# CT_switching.net
KiCad netlist of a schematic drawn in Altium Designer
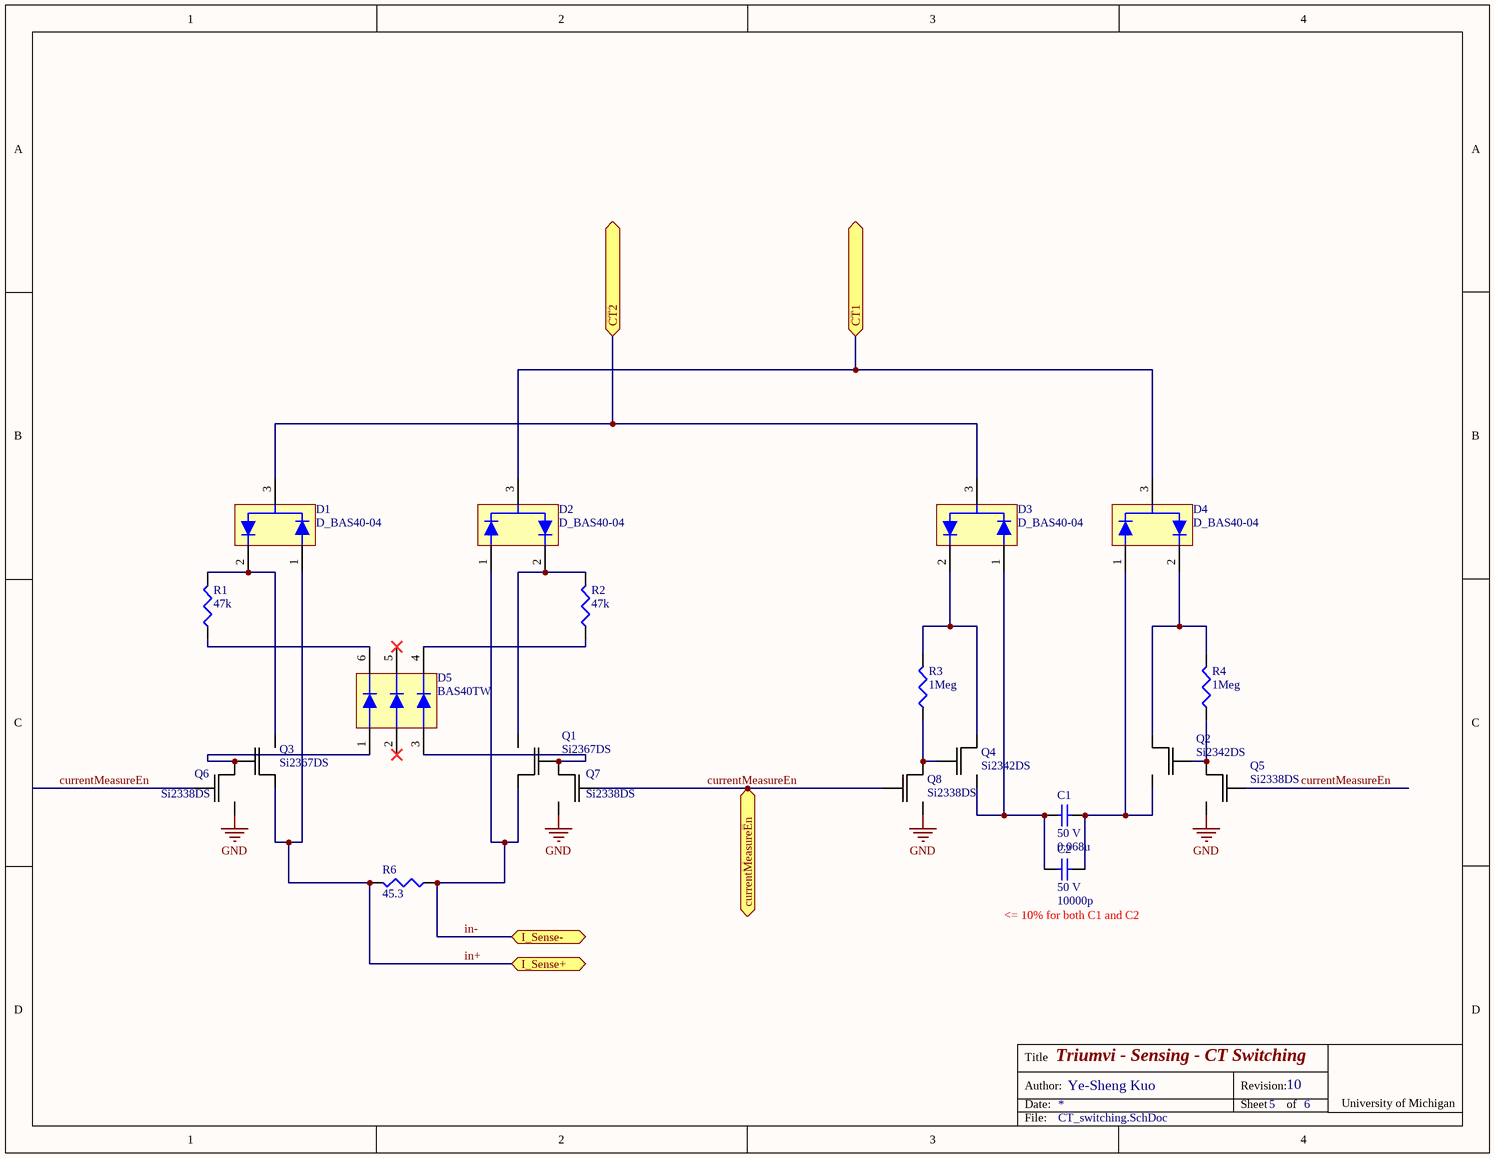
[diagram p0: CT_switching.SchDoc]

(export (version "E")
  (design (tool "Eeschema 10.0.6"))
  (components
    (comp (ref "C1")
      (value "0.068u")
      (footprint "0603")
      (description "0.068µF ±10% 50V Ceramic Capacitor X7R 0603")
      (fields
        (field (name "TOLERANCE") "10%")
        (field (name "VOLTAGE RATED") "50 V")
        (field (name "MANUFACTURER PART NUMBER") "C0603C683K5RACTU")
      )
      (libsource (lib "capacitors") (part "C0603C683K5RACTU"))
    )
    (comp (ref "C2")
      (value "10000p")
      (footprint "0603")
      (description "10000pF ±5% 50V Ceramic Capacitor X7R 0603")
      (fields
        (field (name "TOLERANCE") "5%")
        (field (name "VOLTAGE RATED") "50 V")
        (field (name "MANUFACTURER PART NUMBER") "C0603C103J5RACTU")
      )
      (libsource (lib "capacitors") (part "C0603C103J5RACTU"))
    )
    (comp (ref "D1")
      (value "D_BAS40-04")
      (footprint "SOT23-3")
      (description "SURFACE MOUNT SCHOTTKY BARRIER DIODE")
      (libsource (lib "diodes") (part "D_BAS40-04"))
    )
    (comp (ref "D2")
      (value "D_BAS40-04")
      (footprint "SOT23-3")
      (description "SURFACE MOUNT SCHOTTKY BARRIER DIODE")
      (libsource (lib "") (part "D_BAS40-04_1"))
    )
    (comp (ref "D3")
      (value "D_BAS40-04")
      (footprint "SOT23-3")
      (description "SURFACE MOUNT SCHOTTKY BARRIER DIODE")
      (libsource (lib "diodes") (part "D_BAS40-04"))
    )
    (comp (ref "D4")
      (value "D_BAS40-04")
      (footprint "SOT23-3")
      (description "SURFACE MOUNT SCHOTTKY BARRIER DIODE")
      (libsource (lib "") (part "D_BAS40-04_1"))
    )
    (comp (ref "D5")
      (value "BAS40TW")
      (footprint "SOT-363")
      (description "SURFACE MOUNT SCHOTTKY BARRIER DIODE ARRAYS")
      (libsource (lib "diodes") (part "D_BAS40TW"))
    )
    (comp (ref "Q1")
      (value "Si2367DS")
      (footprint "SOT23-3")
      (description "P-Channel 20 V (D-S) MOSFET")
      (libsource (lib "transistors") (part "Si2367DS"))
    )
    (comp (ref "Q2")
      (value "Si2342DS")
      (footprint "SOT23-3")
      (description "N-Channel 8 V (D-S) MOSFET")
      (libsource (lib "transistors") (part "Si2342DS"))
    )
    (comp (ref "Q3")
      (value "Si2367DS")
      (footprint "SOT23-3")
      (description "P-Channel 20 V (D-S) MOSFET")
      (libsource (lib "transistors") (part "Si2367DS"))
    )
    (comp (ref "Q4")
      (value "Si2342DS")
      (footprint "SOT23-3")
      (description "N-Channel 8 V (D-S) MOSFET")
      (libsource (lib "transistors") (part "Si2342DS"))
    )
    (comp (ref "Q5")
      (value "Si2338DS")
      (footprint "SOT23-3")
      (description "N-Channel 30 V (D-S) MOSFET")
      (libsource (lib "transistors") (part "Si2338DS"))
    )
    (comp (ref "Q6")
      (value "Si2338DS")
      (footprint "SOT23-3")
      (description "N-Channel 30 V (D-S) MOSFET")
      (libsource (lib "transistors") (part "Si2338DS"))
    )
    (comp (ref "Q7")
      (value "Si2338DS")
      (footprint "SOT23-3")
      (description "N-Channel 30 V (D-S) MOSFET")
      (libsource (lib "transistors") (part "Si2338DS"))
    )
    (comp (ref "Q8")
      (value "Si2338DS")
      (footprint "SOT23-3")
      (description "N-Channel 30 V (D-S) MOSFET")
      (libsource (lib "transistors") (part "Si2338DS"))
    )
    (comp (ref "R1")
      (value "47k")
      (footprint "0402")
      (description "RES SMD 47K OHM 1% 1/16W 0402")
      (fields (field (name "TOLERANCE") "1%") (field (name "POWER") "1/16 W"))
      (libsource (lib "resistors") (part "CRCW040247K0FKED"))
    )
    (comp (ref "R2")
      (value "47k")
      (footprint "0402")
      (description "RES SMD 47K OHM 1% 1/16W 0402")
      (fields (field (name "TOLERANCE") "1%") (field (name "POWER") "1/16 W"))
      (libsource (lib "resistors") (part "CRCW040247K0FKED"))
    )
    (comp (ref "R3")
      (value "1Meg")
      (footprint "0402")
      (description "RES SMD 1M OHM 1% 1/16W 0402")
      (fields (field (name "TOLERANCE") "1%") (field (name "POWER") "1/16 W"))
      (libsource (lib "resistors") (part "CRCW04021M00FKED"))
    )
    (comp (ref "R4")
      (value "1Meg")
      (footprint "0402")
      (description "RES SMD 1M OHM 1% 1/16W 0402")
      (fields (field (name "TOLERANCE") "1%") (field (name "POWER") "1/16 W"))
      (libsource (lib "resistors") (part "CRCW04021M00FKED"))
    )
    (comp (ref "R6")
      (value "45.3")
      (footprint "0603")
      (description "RES SMD 45.3 OHM 0.1% 1/6W 0603")
      (fields (field (name "POWER") "1/6 W") (field (name "TOLERANCE") "0.1%"))
      (libsource (lib "resistors") (part "RP73PF1J45R3BTDF"))
    )
  )
  (nets
    (net (code "1") (name "/CT1") (class "Default")
      (node (ref "D2") (pin "3") (pinfunction "3_3") (pintype "passive"))
      (node (ref "D4") (pin "3") (pinfunction "3_3") (pintype "passive"))
    )
    (net (code "2") (name "/CT2") (class "Default")
      (node (ref "D1") (pin "3") (pinfunction "3_3") (pintype "passive"))
      (node (ref "D3") (pin "3") (pinfunction "3_3") (pintype "passive"))
    )
    (net (code "3") (name "/currentMeasureEn") (class "Default")
      (node (ref "Q5") (pin "1") (pinfunction "G_1") (pintype "passive"))
      (node (ref "Q6") (pin "1") (pinfunction "G_1") (pintype "passive"))
      (node (ref "Q7") (pin "1") (pinfunction "G_1") (pintype "passive"))
      (node (ref "Q8") (pin "1") (pinfunction "G_1") (pintype "passive"))
    )
    (net (code "4") (name "/in+") (class "Default")
      (node (ref "D1") (pin "1") (pinfunction "1_1") (pintype "passive"))
      (node (ref "Q3") (pin "3") (pinfunction "D_3") (pintype "passive"))
      (node (ref "R6") (pin "1") (pintype "passive"))
    )
    (net (code "5") (name "/in-") (class "Default")
      (node (ref "D2") (pin "1") (pinfunction "1_1") (pintype "passive"))
      (node (ref "Q1") (pin "3") (pinfunction "D_3") (pintype "passive"))
      (node (ref "R6") (pin "2") (pintype "passive"))
    )
    (net (code "6") (name "GND") (class "Default")
      (node (ref "Q5") (pin "2") (pinfunction "S_2") (pintype "passive"))
      (node (ref "Q6") (pin "2") (pinfunction "S_2") (pintype "passive"))
      (node (ref "Q7") (pin "2") (pinfunction "S_2") (pintype "passive"))
      (node (ref "Q8") (pin "2") (pinfunction "S_2") (pintype "passive"))
    )
    (net (code "7") (name "Net-(D5-Pad4)") (class "Default")
      (node (ref "D5") (pin "4") (pinfunction "4_4") (pintype "passive"))
      (node (ref "R2") (pin "2") (pintype "passive"))
    )
    (net (code "8") (name "Net-(D5-Pad6)") (class "Default")
      (node (ref "D5") (pin "6") (pinfunction "6_6") (pintype "passive"))
      (node (ref "R1") (pin "2") (pintype "passive"))
    )
    (net (code "9") (name "Net-(Q1-G)") (class "Default")
      (node (ref "D5") (pin "3") (pinfunction "3_3") (pintype "passive"))
      (node (ref "Q1") (pin "1") (pinfunction "G_1") (pintype "passive"))
      (node (ref "Q7") (pin "3") (pinfunction "D_3") (pintype "passive"))
    )
    (net (code "10") (name "Net-(Q1-S)") (class "Default")
      (node (ref "D2") (pin "2") (pinfunction "2_2") (pintype "passive"))
      (node (ref "Q1") (pin "2") (pinfunction "S_2") (pintype "passive"))
      (node (ref "R2") (pin "1") (pintype "passive"))
    )
    (net (code "11") (name "Net-(Q2-D)") (class "Default")
      (node (ref "D4") (pin "2") (pinfunction "2_2") (pintype "passive"))
      (node (ref "Q2") (pin "3") (pinfunction "D_3") (pintype "passive"))
      (node (ref "R4") (pin "1") (pintype "passive"))
    )
    (net (code "12") (name "Net-(Q2-G)") (class "Default")
      (node (ref "Q2") (pin "1") (pinfunction "G_1") (pintype "passive"))
      (node (ref "Q5") (pin "3") (pinfunction "D_3") (pintype "passive"))
      (node (ref "R4") (pin "2") (pintype "passive"))
    )
    (net (code "13") (name "Net-(Q2-S)") (class "Default")
      (node (ref "C1") (pin "2") (pintype "passive"))
      (node (ref "C2") (pin "2") (pintype "passive"))
      (node (ref "D4") (pin "1") (pinfunction "1_1") (pintype "passive"))
      (node (ref "Q2") (pin "2") (pinfunction "S_2") (pintype "passive"))
    )
    (net (code "14") (name "Net-(Q3-G)") (class "Default")
      (node (ref "D5") (pin "1") (pinfunction "1_1") (pintype "passive"))
      (node (ref "Q3") (pin "1") (pinfunction "G_1") (pintype "passive"))
      (node (ref "Q6") (pin "3") (pinfunction "D_3") (pintype "passive"))
    )
    (net (code "15") (name "Net-(Q3-S)") (class "Default")
      (node (ref "D1") (pin "2") (pinfunction "2_2") (pintype "passive"))
      (node (ref "Q3") (pin "2") (pinfunction "S_2") (pintype "passive"))
      (node (ref "R1") (pin "1") (pintype "passive"))
    )
    (net (code "16") (name "Net-(Q4-D)") (class "Default")
      (node (ref "D3") (pin "2") (pinfunction "2_2") (pintype "passive"))
      (node (ref "Q4") (pin "3") (pinfunction "D_3") (pintype "passive"))
      (node (ref "R3") (pin "1") (pintype "passive"))
    )
    (net (code "17") (name "Net-(Q4-G)") (class "Default")
      (node (ref "Q4") (pin "1") (pinfunction "G_1") (pintype "passive"))
      (node (ref "Q8") (pin "3") (pinfunction "D_3") (pintype "passive"))
      (node (ref "R3") (pin "2") (pintype "passive"))
    )
    (net (code "18") (name "Net-(Q4-S)") (class "Default")
      (node (ref "C1") (pin "1") (pintype "passive"))
      (node (ref "C2") (pin "1") (pintype "passive"))
      (node (ref "D3") (pin "1") (pinfunction "1_1") (pintype "passive"))
      (node (ref "Q4") (pin "2") (pinfunction "S_2") (pintype "passive"))
    )
    (net (code "19") (name "unconnected-(D5-Pad2)") (class "Default")
      (node (ref "D5") (pin "2") (pinfunction "2_2") (pintype "passive+no_connect"))
    )
    (net (code "20") (name "unconnected-(D5-Pad5)") (class "Default")
      (node (ref "D5") (pin "5") (pinfunction "5_5") (pintype "passive+no_connect"))
    )
  )
)
